# Wi-Fi_Button_v1.net
KiCad netlist of a schematic drawn in EAGLE
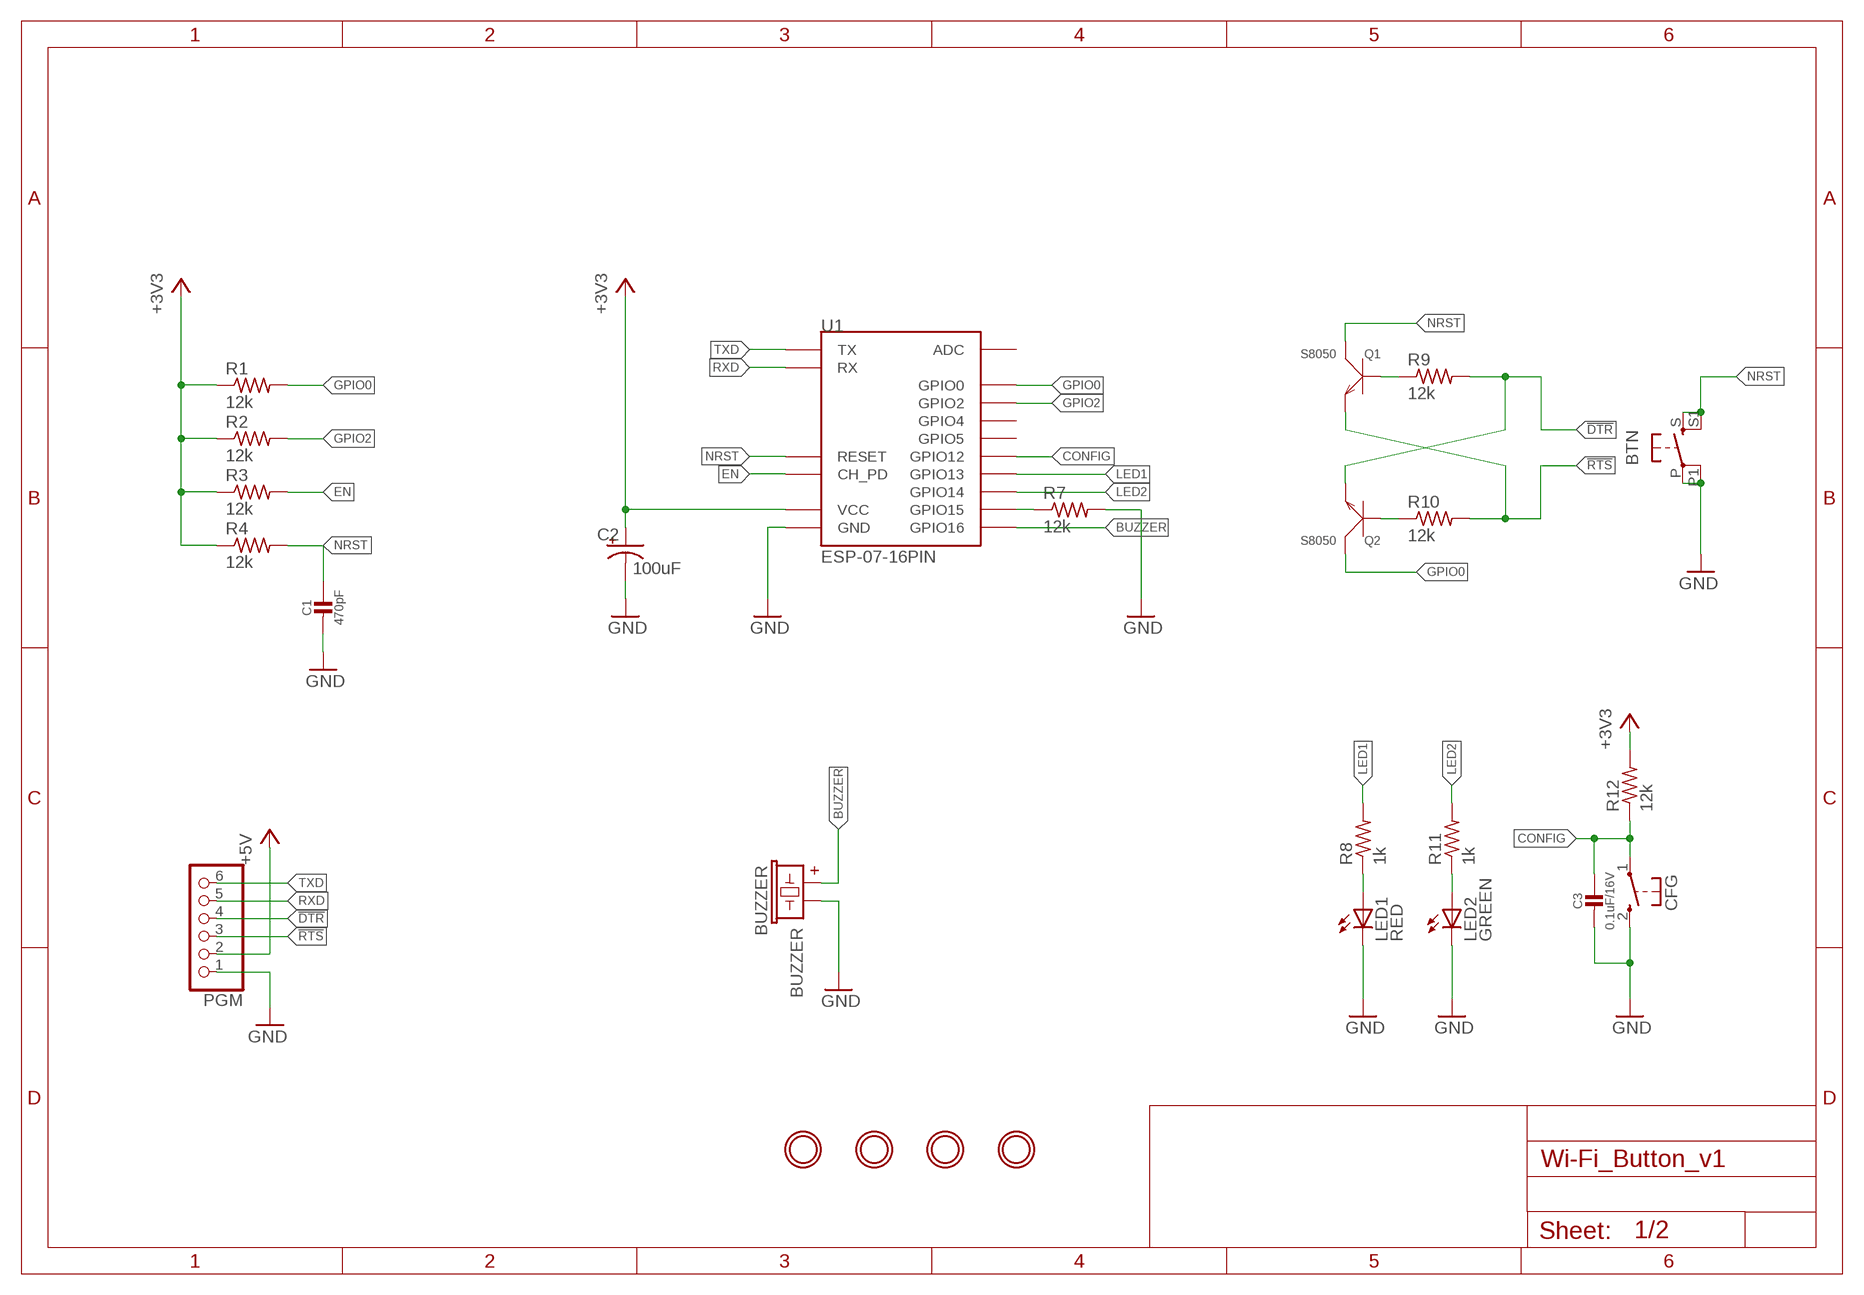
[diagram p0: schematic, sheet 1]
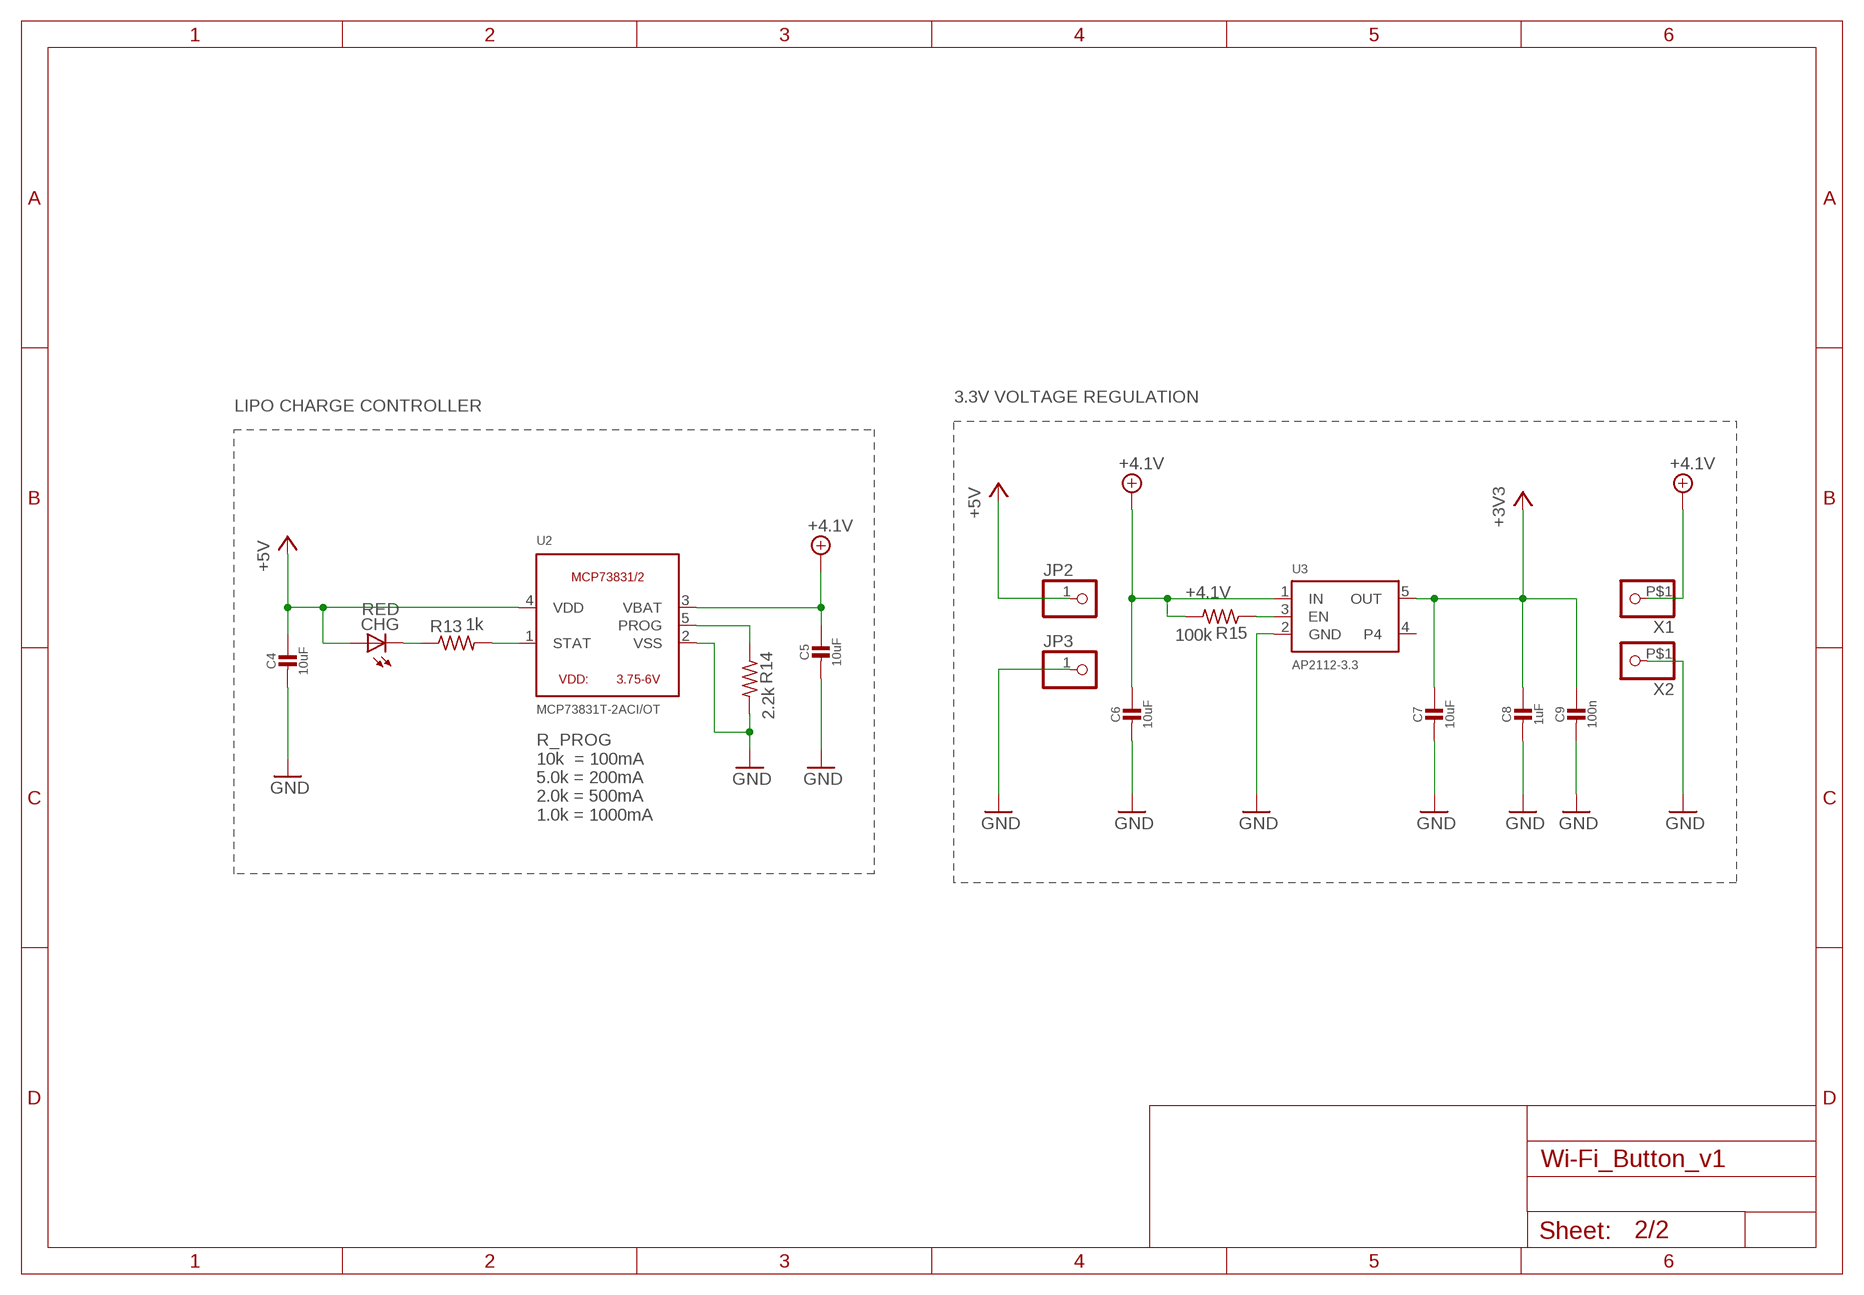
[diagram p1: schematic, sheet 2]

(export (version "E")
  (design (tool "Eeschema 10.0.6"))
  (components
    (comp (ref "$H1")
      (value "MOUNTINGHOLE2.5")
      (footprint "eagle-import:MOUNTINGHOLE_2.5_PLATED")
      (libsource (lib "eagle-import") (part "MOUNTINGHOLE2.5"))
    )
    (comp (ref "$H2")
      (value "MOUNTINGHOLE2.5")
      (footprint "eagle-import:MOUNTINGHOLE_2.5_PLATED")
      (libsource (lib "eagle-import") (part "MOUNTINGHOLE2.5"))
    )
    (comp (ref "$H3")
      (value "MOUNTINGHOLE2.5")
      (footprint "eagle-import:MOUNTINGHOLE_2.5_PLATED")
      (libsource (lib "eagle-import") (part "MOUNTINGHOLE2.5"))
    )
    (comp (ref "$H4")
      (value "MOUNTINGHOLE2.5")
      (footprint "eagle-import:MOUNTINGHOLE_2.5_PLATED")
      (libsource (lib "eagle-import") (part "MOUNTINGHOLE2.5"))
    )
    (comp (ref "BTN")
      (value "SWITRONIC_12XXS")
      (footprint "eagle-import:SWITRONIC_12X12")
      (libsource (lib "eagle-import") (part "SWITRONIC_12XXS"))
    )
    (comp (ref "BUZZER")
      (value "BUZZER")
      (footprint "eagle-import:BUUZER-HN9605B")
      (libsource (lib "eagle-import") (part "BUZZER"))
    )
    (comp (ref "C1")
      (value "470pF")
      (footprint "eagle-import:_0805")
      (libsource (lib "eagle-import") (part "CAP_CERAMIC_0805"))
    )
    (comp (ref "C2")
      (value "100uF")
      (footprint "eagle-import:A_3216-18R")
      (libsource (lib "eagle-import") (part "CPOL-USA/3216-18R"))
    )
    (comp (ref "C3")
      (value "0.1uF/16V")
      (footprint "eagle-import:_0805")
      (libsource (lib "eagle-import") (part "CAP_CERAMIC_0805"))
    )
    (comp (ref "CFG")
      (value "KSS-2EG4430")
      (footprint "eagle-import:KSS-2EG4430")
      (libsource (lib "eagle-import") (part "KSS-2EG4430"))
    )
    (comp (ref "LED1")
      (value "RED")
      (footprint "eagle-import:CHIP-LED0805")
      (libsource (lib "eagle-import") (part "LEDCHIP-LED0805"))
    )
    (comp (ref "LED2")
      (value "GREEN")
      (footprint "eagle-import:CHIP-LED0805")
      (libsource (lib "eagle-import") (part "LEDCHIP-LED0805"))
    )
    (comp (ref "PGM")
      (value "PINHD-1X6")
      (footprint "eagle-import:1X06")
      (libsource (lib "eagle-import") (part "PINHD-1X6"))
    )
    (comp (ref "Q1")
      (value "S8050")
      (footprint "eagle-import:SOT-23")
      (fields (field (name "MF") "JCET"))
      (libsource (lib "eagle-import") (part "SMD-TRANSISTORS-NPN-25V-500MW(SOT-23)"))
    )
    (comp (ref "Q2")
      (value "S8050")
      (footprint "eagle-import:SOT-23")
      (fields (field (name "MF") "JCET"))
      (libsource (lib "eagle-import") (part "SMD-TRANSISTORS-NPN-25V-500MW(SOT-23)"))
    )
    (comp (ref "R1")
      (value "12k")
      (footprint "eagle-import:M0805")
      (libsource (lib "eagle-import") (part "R-US_M0805"))
    )
    (comp (ref "R2")
      (value "12k")
      (footprint "eagle-import:M0805")
      (libsource (lib "eagle-import") (part "R-US_M0805"))
    )
    (comp (ref "R3")
      (value "12k")
      (footprint "eagle-import:M0805")
      (libsource (lib "eagle-import") (part "R-US_M0805"))
    )
    (comp (ref "R4")
      (value "12k")
      (footprint "eagle-import:M0805")
      (libsource (lib "eagle-import") (part "R-US_M0805"))
    )
    (comp (ref "R7")
      (value "12k")
      (footprint "eagle-import:M0805")
      (libsource (lib "eagle-import") (part "R-US_M0805"))
    )
    (comp (ref "R8")
      (value "1k")
      (footprint "eagle-import:M0805")
      (libsource (lib "eagle-import") (part "R-US_M0805"))
    )
    (comp (ref "R9")
      (value "12k")
      (footprint "eagle-import:M0805")
      (libsource (lib "eagle-import") (part "R-US_M0805"))
    )
    (comp (ref "R10")
      (value "12k")
      (footprint "eagle-import:M0805")
      (libsource (lib "eagle-import") (part "R-US_M0805"))
    )
    (comp (ref "R11")
      (value "1k")
      (footprint "eagle-import:M0805")
      (libsource (lib "eagle-import") (part "R-US_M0805"))
    )
    (comp (ref "R12")
      (value "12k")
      (footprint "eagle-import:M0805")
      (libsource (lib "eagle-import") (part "R-US_M0805"))
    )
    (comp (ref "U1")
      (value "ESP-07-16PIN")
      (footprint "eagle-import:ESP-07-16PIN")
      (libsource (lib "eagle-import") (part "ESP-07-16PIN"))
    )
    (comp (ref "C4")
      (value "10uF")
      (footprint "eagle-import:_0805")
      (libsource (lib "eagle-import") (part "CAP_CERAMIC_0805"))
    )
    (comp (ref "C5")
      (value "10uF")
      (footprint "eagle-import:_0805")
      (libsource (lib "eagle-import") (part "CAP_CERAMIC_0805"))
    )
    (comp (ref "C6")
      (value "10uF")
      (footprint "eagle-import:_0805")
      (libsource (lib "eagle-import") (part "CAP_CERAMIC_0805"))
    )
    (comp (ref "C7")
      (value "10uF")
      (footprint "eagle-import:_0805")
      (libsource (lib "eagle-import") (part "CAP_CERAMIC_0805"))
    )
    (comp (ref "C8")
      (value "1uF")
      (footprint "eagle-import:_0805")
      (libsource (lib "eagle-import") (part "CAP_CERAMIC_0805"))
    )
    (comp (ref "C9")
      (value "100n")
      (footprint "eagle-import:_0805")
      (libsource (lib "eagle-import") (part "CAP_CERAMIC_0805"))
    )
    (comp (ref "CHG")
      (value "RED")
      (footprint "eagle-import:CHIP-LED0805")
      (libsource (lib "eagle-import") (part "LEDCHIP-LED0805"))
    )
    (comp (ref "JP2")
      (value "HEADER-1X1-SMD_MASKHELD_2X2MM")
      (footprint "eagle-import:1X01_SMD_MASKHELD_2X2MM")
      (libsource (lib "eagle-import") (part "HEADER-1X1-SMD_MASKHELD_2X2MM"))
    )
    (comp (ref "JP3")
      (value "HEADER-1X1-SMD_MASKHELD_2X2MM")
      (footprint "eagle-import:1X01_SMD_MASKHELD_2X2MM")
      (libsource (lib "eagle-import") (part "HEADER-1X1-SMD_MASKHELD_2X2MM"))
    )
    (comp (ref "R13")
      (value "1k")
      (footprint "eagle-import:M0805")
      (libsource (lib "eagle-import") (part "resistor_R-US_M0805"))
    )
    (comp (ref "R14")
      (value "2.2k")
      (footprint "eagle-import:M0805")
      (libsource (lib "eagle-import") (part "resistor_R-US_M0805"))
    )
    (comp (ref "R15")
      (value "100k")
      (footprint "eagle-import:M0805")
      (libsource (lib "eagle-import") (part "resistor_R-US_M0805"))
    )
    (comp (ref "U2")
      (value "MCP73831T-2ACI/OT")
      (footprint "eagle-import:SOT23-5")
      (libsource (lib "eagle-import") (part "MCP73831/2"))
    )
    (comp (ref "U3")
      (value "AP2112-3.3")
      (footprint "eagle-import:SOT23-5")
      (libsource (lib "eagle-import") (part "VREG_SOT23-5"))
    )
    (comp (ref "X1")
      (value "A23_PCB_MOUNT")
      (footprint "eagle-import:A23_PCB_MOUNT")
      (libsource (lib "eagle-import") (part "A23_PCB_MOUNT"))
    )
    (comp (ref "X2")
      (value "A23_PCB_MOUNT")
      (footprint "eagle-import:A23_PCB_MOUNT")
      (libsource (lib "eagle-import") (part "A23_PCB_MOUNT"))
    )
  )
  (nets
    (net (code "1") (name "+3V3") (class "Default")
      (node (ref "C2") (pin "+") (pinfunction "+_+") (pintype "passive"))
      (node (ref "C7") (pin "1") (pinfunction "1_1") (pintype "passive"))
      (node (ref "C8") (pin "1") (pinfunction "1_1") (pintype "passive"))
      (node (ref "C9") (pin "1") (pinfunction "1_1") (pintype "passive"))
      (node (ref "R1") (pin "1") (pinfunction "1_1") (pintype "passive"))
      (node (ref "R12") (pin "2") (pinfunction "2_2") (pintype "passive"))
      (node (ref "R2") (pin "1") (pinfunction "1_1") (pintype "passive"))
      (node (ref "R3") (pin "1") (pinfunction "1_1") (pintype "passive"))
      (node (ref "R4") (pin "1") (pinfunction "1_1") (pintype "passive"))
      (node (ref "U1") (pin "VCC") (pinfunction "VCC_VCC") (pintype "bidirectional"))
      (node (ref "U3") (pin "5") (pinfunction "OUT_5") (pintype "power_in"))
    )
    (net (code "2") (name "+4.1V") (class "Default")
      (node (ref "C5") (pin "1") (pinfunction "1_1") (pintype "passive"))
      (node (ref "C6") (pin "1") (pinfunction "1_1") (pintype "passive"))
      (node (ref "R15") (pin "2") (pinfunction "2_2") (pintype "passive"))
      (node (ref "U2") (pin "3") (pinfunction "VBAT_3") (pintype "power_in"))
      (node (ref "U3") (pin "1") (pinfunction "IN_1") (pintype "power_in"))
      (node (ref "X1") (pin "P$1") (pinfunction "1_P$1") (pintype "passive"))
    )
    (net (code "3") (name "+5V") (class "Default")
      (node (ref "C4") (pin "1") (pinfunction "1_1") (pintype "passive"))
      (node (ref "CHG") (pin "A") (pinfunction "A_A") (pintype "passive"))
      (node (ref "JP2") (pin "1") (pinfunction "1_1") (pintype "passive"))
      (node (ref "PGM") (pin "2") (pinfunction "2_2") (pintype "passive"))
      (node (ref "U2") (pin "4") (pinfunction "VDD_4") (pintype "power_in"))
    )
    (net (code "4") (name "BUZZER") (class "Default")
      (node (ref "BUZZER") (pin "1") (pinfunction "1_1") (pintype "passive"))
      (node (ref "U1") (pin "GPIO16") (pinfunction "GPIO16_GPIO16") (pintype "bidirectional"))
    )
    (net (code "5") (name "CONFIG") (class "Default")
      (node (ref "C3") (pin "1") (pinfunction "1_1") (pintype "passive"))
      (node (ref "CFG") (pin "1") (pinfunction "P_1") (pintype "passive"))
      (node (ref "R12") (pin "1") (pinfunction "1_1") (pintype "passive"))
      (node (ref "U1") (pin "GPIO12") (pinfunction "GPIO12_GPIO12") (pintype "bidirectional"))
    )
    (net (code "6") (name "EN") (class "Default")
      (node (ref "R3") (pin "2") (pinfunction "2_2") (pintype "passive"))
      (node (ref "U1") (pin "CH_PD") (pinfunction "CH_PD_CH_PD") (pintype "bidirectional"))
    )
    (net (code "7") (name "GND") (class "Default")
      (node (ref "BTN") (pin "P") (pinfunction "P_P") (pintype "passive"))
      (node (ref "BTN") (pin "P1") (pinfunction "P1_P1") (pintype "passive"))
      (node (ref "BUZZER") (pin "2") (pinfunction "2_2") (pintype "passive"))
      (node (ref "C1") (pin "2") (pinfunction "2_2") (pintype "passive"))
      (node (ref "C2") (pin "-") (pinfunction "-_-") (pintype "passive"))
      (node (ref "C3") (pin "2") (pinfunction "2_2") (pintype "passive"))
      (node (ref "C4") (pin "2") (pinfunction "2_2") (pintype "passive"))
      (node (ref "C5") (pin "2") (pinfunction "2_2") (pintype "passive"))
      (node (ref "C6") (pin "2") (pinfunction "2_2") (pintype "passive"))
      (node (ref "C7") (pin "2") (pinfunction "2_2") (pintype "passive"))
      (node (ref "C8") (pin "2") (pinfunction "2_2") (pintype "passive"))
      (node (ref "C9") (pin "2") (pinfunction "2_2") (pintype "passive"))
      (node (ref "CFG") (pin "2") (pinfunction "S_2") (pintype "passive"))
      (node (ref "JP3") (pin "1") (pinfunction "1_1") (pintype "passive"))
      (node (ref "LED1") (pin "C") (pinfunction "C_C") (pintype "passive"))
      (node (ref "LED2") (pin "C") (pinfunction "C_C") (pintype "passive"))
      (node (ref "PGM") (pin "1") (pinfunction "1_1") (pintype "passive"))
      (node (ref "R14") (pin "2") (pinfunction "2_2") (pintype "passive"))
      (node (ref "R7") (pin "2") (pinfunction "2_2") (pintype "passive"))
      (node (ref "U1") (pin "GND") (pinfunction "GND_GND") (pintype "bidirectional"))
      (node (ref "U2") (pin "2") (pinfunction "VSS_2") (pintype "power_in"))
      (node (ref "U3") (pin "2") (pinfunction "GND_2") (pintype "power_in"))
      (node (ref "X2") (pin "P$1") (pinfunction "1_P$1") (pintype "passive"))
    )
    (net (code "8") (name "GPIO0") (class "Default")
      (node (ref "Q2") (pin "3") (pinfunction "C_3") (pintype "passive"))
      (node (ref "R1") (pin "2") (pinfunction "2_2") (pintype "passive"))
      (node (ref "U1") (pin "GPIO0") (pinfunction "GPIO0_GPIO0") (pintype "bidirectional"))
    )
    (net (code "9") (name "GPIO2") (class "Default")
      (node (ref "R2") (pin "2") (pinfunction "2_2") (pintype "passive"))
      (node (ref "U1") (pin "GPIO2") (pinfunction "GPIO2_GPIO2") (pintype "bidirectional"))
    )
    (net (code "10") (name "LED1") (class "Default")
      (node (ref "R8") (pin "2") (pinfunction "2_2") (pintype "passive"))
      (node (ref "U1") (pin "GPIO13") (pinfunction "GPIO13_GPIO13") (pintype "bidirectional"))
    )
    (net (code "11") (name "LED2") (class "Default")
      (node (ref "R11") (pin "2") (pinfunction "2_2") (pintype "passive"))
      (node (ref "U1") (pin "GPIO14") (pinfunction "GPIO14_GPIO14") (pintype "bidirectional"))
    )
    (net (code "12") (name "NRST") (class "Default")
      (node (ref "BTN") (pin "S") (pinfunction "S_S") (pintype "passive"))
      (node (ref "BTN") (pin "S1") (pinfunction "S1_S1") (pintype "passive"))
      (node (ref "C1") (pin "1") (pinfunction "1_1") (pintype "passive"))
      (node (ref "Q1") (pin "3") (pinfunction "C_3") (pintype "passive"))
      (node (ref "R4") (pin "2") (pinfunction "2_2") (pintype "passive"))
      (node (ref "U1") (pin "REST") (pinfunction "RESET_REST") (pintype "bidirectional"))
    )
    (net (code "13") (name "Net-(CHG-PadC)") (class "Default")
      (node (ref "CHG") (pin "C") (pinfunction "C_C") (pintype "passive"))
      (node (ref "R13") (pin "1") (pinfunction "1_1") (pintype "passive"))
    )
    (net (code "14") (name "Net-(LED1-PadA)") (class "Default")
      (node (ref "LED1") (pin "A") (pinfunction "A_A") (pintype "passive"))
      (node (ref "R8") (pin "1") (pinfunction "1_1") (pintype "passive"))
    )
    (net (code "15") (name "Net-(LED2-PadA)") (class "Default")
      (node (ref "LED2") (pin "A") (pinfunction "A_A") (pintype "passive"))
      (node (ref "R11") (pin "1") (pinfunction "1_1") (pintype "passive"))
    )
    (net (code "16") (name "Net-(Q1-B)") (class "Default")
      (node (ref "Q1") (pin "1") (pinfunction "B_1") (pintype "passive"))
      (node (ref "R9") (pin "1") (pinfunction "1_1") (pintype "passive"))
    )
    (net (code "17") (name "Net-(Q2-B)") (class "Default")
      (node (ref "Q2") (pin "1") (pinfunction "B_1") (pintype "passive"))
      (node (ref "R10") (pin "1") (pinfunction "1_1") (pintype "passive"))
    )
    (net (code "18") (name "Net-(R7-Pad1)") (class "Default")
      (node (ref "R7") (pin "1") (pinfunction "1_1") (pintype "passive"))
      (node (ref "U1") (pin "GPIO15") (pinfunction "GPIO15_GPIO15") (pintype "bidirectional"))
    )
    (net (code "19") (name "Net-(U2-PROG)") (class "Default")
      (node (ref "R14") (pin "1") (pinfunction "1_1") (pintype "passive"))
      (node (ref "U2") (pin "5") (pinfunction "PROG_5") (pintype "input"))
    )
    (net (code "20") (name "Net-(U2-STAT)") (class "Default")
      (node (ref "R13") (pin "2") (pinfunction "2_2") (pintype "passive"))
      (node (ref "U2") (pin "1") (pinfunction "STAT_1") (pintype "output"))
    )
    (net (code "21") (name "Net-(U3-EN)") (class "Default")
      (node (ref "R15") (pin "1") (pinfunction "1_1") (pintype "passive"))
      (node (ref "U3") (pin "3") (pinfunction "EN_3") (pintype "input"))
    )
    (net (code "22") (name "RXD") (class "Default")
      (node (ref "PGM") (pin "5") (pinfunction "5_5") (pintype "passive"))
      (node (ref "U1") (pin "RX") (pinfunction "RX_RX") (pintype "bidirectional"))
    )
    (net (code "23") (name "TXD") (class "Default")
      (node (ref "PGM") (pin "6") (pinfunction "6_6") (pintype "passive"))
      (node (ref "U1") (pin "TX") (pinfunction "TX_TX") (pintype "bidirectional"))
    )
    (net (code "24") (name "unconnected-(U1-PadADC)") (class "Default")
      (node (ref "U1") (pin "ADC") (pinfunction "ADC_ADC") (pintype "bidirectional"))
    )
    (net (code "25") (name "unconnected-(U1-PadGPIO4)") (class "Default")
      (node (ref "U1") (pin "GPIO4") (pinfunction "GPIO4_GPIO4") (pintype "bidirectional"))
    )
    (net (code "26") (name "unconnected-(U1-PadGPIO5)") (class "Default")
      (node (ref "U1") (pin "GPIO5") (pinfunction "GPIO5_GPIO5") (pintype "bidirectional"))
    )
    (net (code "27") (name "unconnected-(U3-P4-Pad4)") (class "Default")
      (node (ref "U3") (pin "4") (pinfunction "P4_4") (pintype "bidirectional"))
    )
    (net (code "28") (name "~{DTR}") (class "Default")
      (node (ref "PGM") (pin "4") (pinfunction "4_4") (pintype "passive"))
      (node (ref "Q2") (pin "2") (pinfunction "E_2") (pintype "passive"))
      (node (ref "R9") (pin "2") (pinfunction "2_2") (pintype "passive"))
    )
    (net (code "29") (name "~{RTS}") (class "Default")
      (node (ref "PGM") (pin "3") (pinfunction "3_3") (pintype "passive"))
      (node (ref "Q1") (pin "2") (pinfunction "E_2") (pintype "passive"))
      (node (ref "R10") (pin "2") (pinfunction "2_2") (pintype "passive"))
    )
  )
)
